# reciever.net
KiCad netlist of a schematic drawn in EAGLE
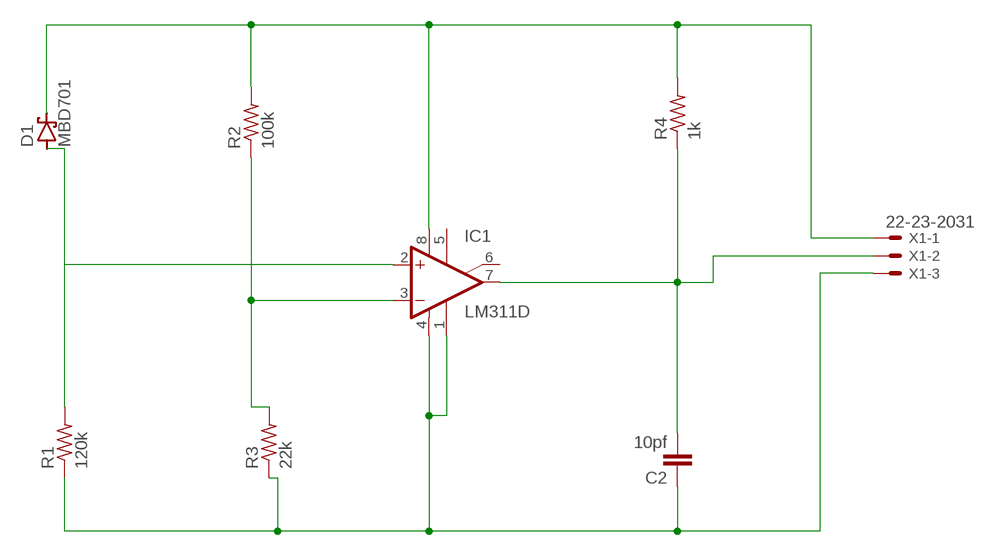
[diagram p0: schematic, sheet 1]

(export (version "E")
  (design (tool "Eeschema 10.0.6"))
  (components
    (comp (ref "C2")
      (value "10pf")
      (footprint "eagle-import:C2.5-2")
      (libsource (lib "eagle-import") (part "C2.5/2"))
    )
    (comp (ref "D1")
      (value "MBD701")
      (footprint "eagle-import:TO92H")
      (libsource (lib "eagle-import") (part "MBD701"))
    )
    (comp (ref "IC1")
      (value "LM311D")
      (footprint "eagle-import:SO08")
      (libsource (lib "eagle-import") (part "LM311D"))
    )
    (comp (ref "R1")
      (value "120k")
      (footprint "eagle-import:0207_10")
      (libsource (lib "eagle-import") (part "R-US_0207/10"))
    )
    (comp (ref "R2")
      (value "100k")
      (footprint "eagle-import:0207_10")
      (libsource (lib "eagle-import") (part "R-US_0207/10"))
    )
    (comp (ref "R3")
      (value "22k")
      (footprint "eagle-import:0207_10")
      (libsource (lib "eagle-import") (part "R-US_0207/10"))
    )
    (comp (ref "R4")
      (value "1k")
      (footprint "eagle-import:0207_10")
      (libsource (lib "eagle-import") (part "R-US_0207/10"))
    )
    (comp (ref "X1")
      (value "22-23-2031")
      (footprint "eagle-import:22-23-2031")
      (fields (field (name "MF") "MOLEX"))
      (libsource (lib "eagle-import") (part "22-23-2031"))
    )
  )
  (nets
    (net (code "1") (name "Net-(D1-A)") (class "Default")
      (node (ref "D1") (pin "1") (pinfunction "A_1") (pintype "passive"))
      (node (ref "IC1") (pin "2") (pinfunction "+IN_2") (pintype "input"))
      (node (ref "R1") (pin "2") (pinfunction "2_2") (pintype "passive"))
    )
    (net (code "2") (name "Net-(D1-C)") (class "Default")
      (node (ref "D1") (pin "2") (pinfunction "C_2") (pintype "passive"))
      (node (ref "IC1") (pin "8") (pinfunction "V+_8") (pintype "power_in"))
      (node (ref "R2") (pin "2") (pinfunction "2_2") (pintype "passive"))
      (node (ref "R4") (pin "2") (pinfunction "2_2") (pintype "passive"))
      (node (ref "X1") (pin "1") (pinfunction "S_1") (pintype "passive"))
    )
    (net (code "3") (name "Net-(IC1--IN)") (class "Default")
      (node (ref "IC1") (pin "3") (pinfunction "-IN_3") (pintype "input"))
      (node (ref "R2") (pin "1") (pinfunction "1_1") (pintype "passive"))
      (node (ref "R3") (pin "2") (pinfunction "2_2") (pintype "passive"))
    )
    (net (code "4") (name "Net-(IC1-GND)") (class "Default")
      (node (ref "C2") (pin "1") (pinfunction "1_1") (pintype "passive"))
      (node (ref "IC1") (pin "1") (pinfunction "GND_1") (pintype "passive"))
      (node (ref "IC1") (pin "4") (pinfunction "V-_4") (pintype "power_in"))
      (node (ref "R1") (pin "1") (pinfunction "1_1") (pintype "passive"))
      (node (ref "R3") (pin "1") (pinfunction "1_1") (pintype "passive"))
      (node (ref "X1") (pin "3") (pinfunction "S_3") (pintype "passive"))
    )
    (net (code "5") (name "Net-(IC1-OUT)") (class "Default")
      (node (ref "C2") (pin "2") (pinfunction "2_2") (pintype "passive"))
      (node (ref "IC1") (pin "7") (pinfunction "OUT_7") (pintype "output"))
      (node (ref "R4") (pin "1") (pinfunction "1_1") (pintype "passive"))
      (node (ref "X1") (pin "2") (pinfunction "S_2") (pintype "passive"))
    )
    (net (code "6") (name "unconnected-(IC1-ON-Pad5)") (class "Default")
      (node (ref "IC1") (pin "5") (pinfunction "ON_5") (pintype "passive"))
    )
    (net (code "7") (name "unconnected-(IC1-ON{slash}STR-Pad6)") (class "Default")
      (node (ref "IC1") (pin "6") (pinfunction "ON/STR_6") (pintype "passive"))
    )
  )
)
